# 17__schdoc.net
KiCad netlist of a schematic drawn in Altium Designer
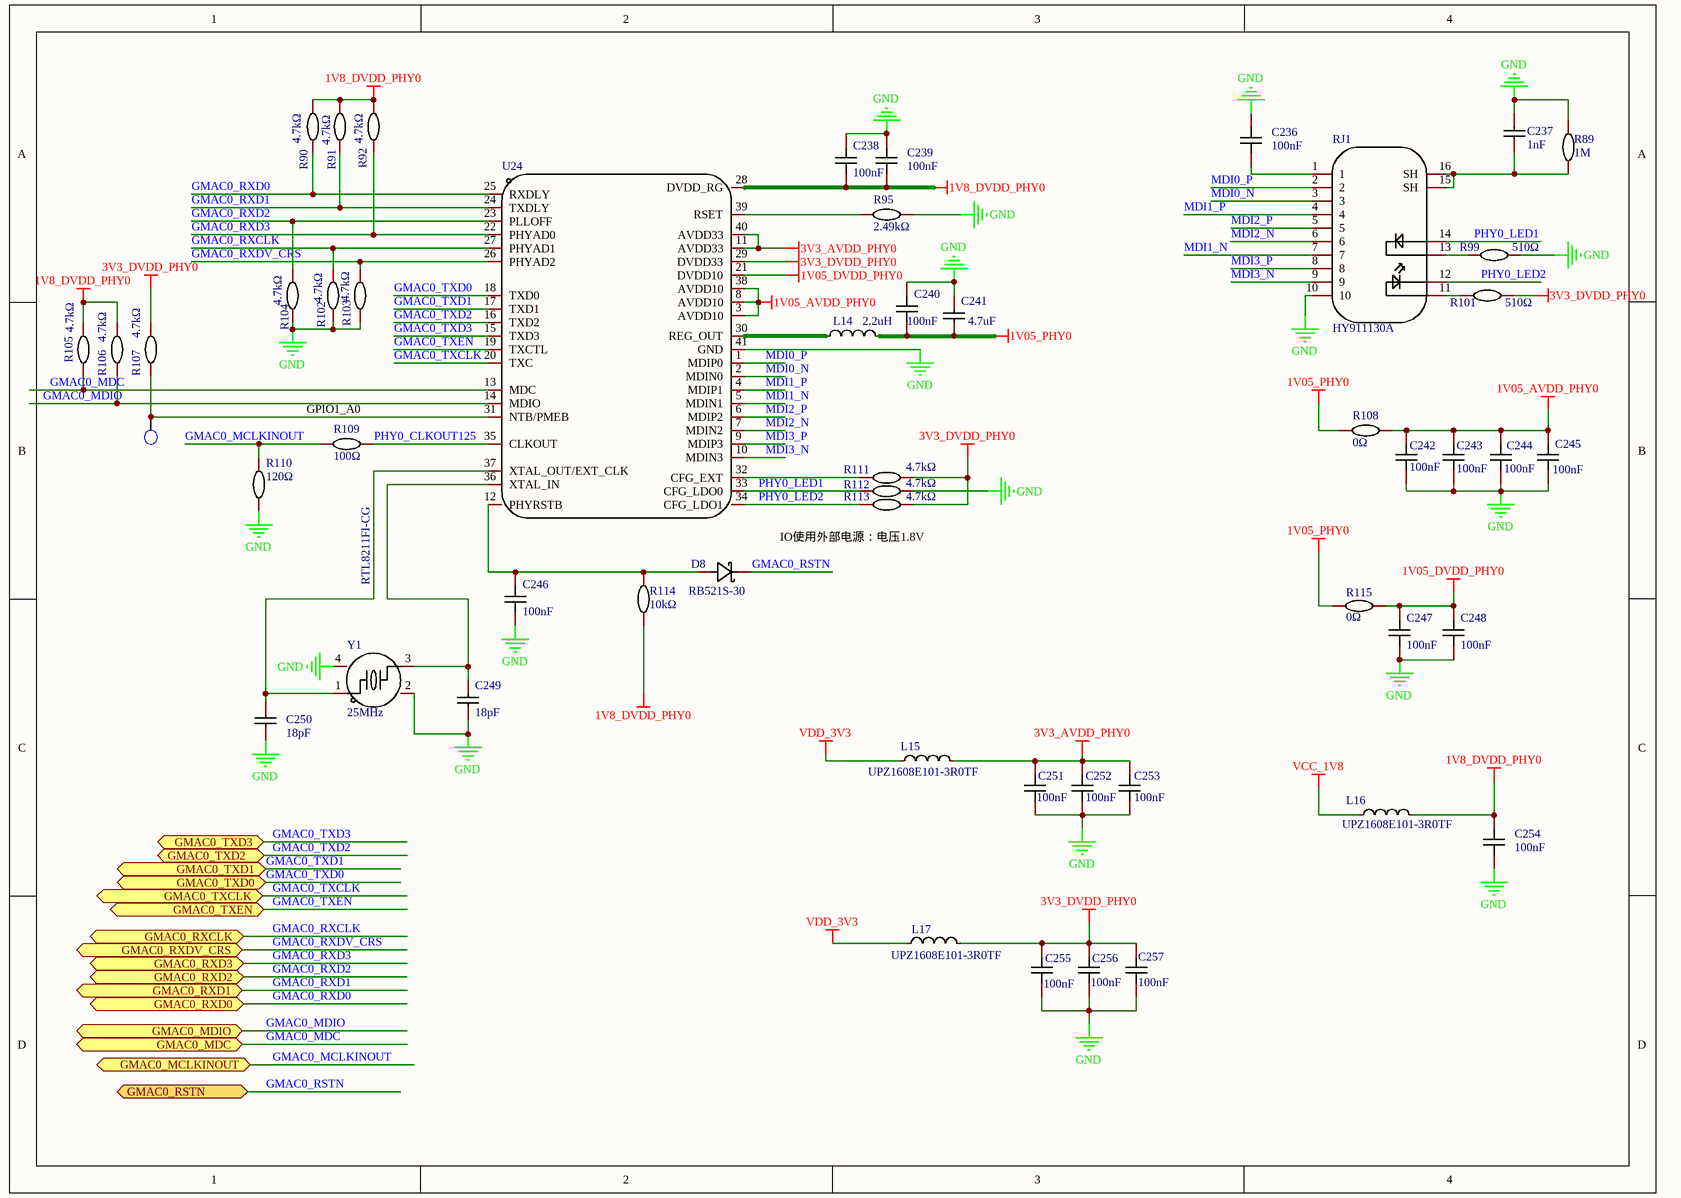
[diagram p0: 17_网口接口.schdoc.schdoc]

(export (version "E")
  (design (tool "Eeschema 10.0.6"))
  (components
    (comp (ref "C236")
      (value "100nF")
      (footprint "C0603")
      (fields
        (field (name "NAME") "100nF")
        (field (name "MANUFACTURER") "YAGEO(国巨)")
        (field (name "MANUFACTURER PART") "CC0603KRX7R9BB104")
        (field (name "TOLERANCE") "±10%")
      )
      (libsource (lib "altium-import") (part "root_1_CC0603KRX7R9BB104_"))
    )
    (comp (ref "C237")
      (value "1nF")
      (footprint "C0603")
      (fields
        (field (name "NAME") "1nF")
        (field (name "MANUFACTURER") "YAGEO(国巨)")
        (field (name "MANUFACTURER PART") "CC0603KRX7R9BB102")
        (field (name "TOLERANCE") "±10%")
      )
      (libsource (lib "altium-import") (part "root_3_CC0603KRX7R9BB102_"))
    )
    (comp (ref "C238")
      (value "100nF")
      (footprint "C0603")
      (fields
        (field (name "NAME") "100nF")
        (field (name "MANUFACTURER") "YAGEO(国巨)")
        (field (name "MANUFACTURER PART") "CC0603KRX7R9BB104")
        (field (name "TOLERANCE") "±10%")
      )
      (libsource (lib "altium-import") (part "root_1_CC0603KRX7R9BB104_"))
    )
    (comp (ref "C239")
      (value "100nF")
      (footprint "C0603")
      (fields
        (field (name "NAME") "100nF")
        (field (name "MANUFACTURER") "YAGEO(国巨)")
        (field (name "MANUFACTURER PART") "CC0603KRX7R9BB104")
        (field (name "TOLERANCE") "±10%")
      )
      (libsource (lib "altium-import") (part "root_1_CC0603KRX7R9BB104_"))
    )
    (comp (ref "C240")
      (value "100nF")
      (footprint "C0603")
      (fields
        (field (name "NAME") "100nF")
        (field (name "MANUFACTURER") "YAGEO(国巨)")
        (field (name "MANUFACTURER PART") "CC0603KRX7R9BB104")
        (field (name "TOLERANCE") "±10%")
      )
      (libsource (lib "altium-import") (part "root_1_CC0603KRX7R9BB104_"))
    )
    (comp (ref "C241")
      (value "4.7uF")
      (footprint "C0603")
      (fields
        (field (name "NAME") "4.7uF")
        (field (name "MANUFACTURER PART") "CL10A475KO8NNNC")
        (field (name "MANUFACTURER") "SAMSUNG(三星)")
        (field (name "TOLERANCE") "±10%")
      )
      (libsource (lib "altium-import") (part "root_1_CL10A475KO8NNNC_"))
    )
    (comp (ref "C242")
      (value "100nF")
      (footprint "C0603")
      (fields
        (field (name "NAME") "100nF")
        (field (name "MANUFACTURER") "YAGEO(国巨)")
        (field (name "MANUFACTURER PART") "CC0603KRX7R9BB104")
        (field (name "TOLERANCE") "±10%")
      )
      (libsource (lib "altium-import") (part "root_1_CC0603KRX7R9BB104_"))
    )
    (comp (ref "C243")
      (value "100nF")
      (footprint "C0603")
      (fields
        (field (name "NAME") "100nF")
        (field (name "MANUFACTURER") "YAGEO(国巨)")
        (field (name "MANUFACTURER PART") "CC0603KRX7R9BB104")
        (field (name "TOLERANCE") "±10%")
      )
      (libsource (lib "altium-import") (part "root_1_CC0603KRX7R9BB104_"))
    )
    (comp (ref "C244")
      (value "100nF")
      (footprint "C0603")
      (fields
        (field (name "NAME") "100nF")
        (field (name "MANUFACTURER") "YAGEO(国巨)")
        (field (name "MANUFACTURER PART") "CC0603KRX7R9BB104")
        (field (name "TOLERANCE") "±10%")
      )
      (libsource (lib "altium-import") (part "root_1_CC0603KRX7R9BB104_"))
    )
    (comp (ref "C245")
      (value "100nF")
      (footprint "C0603")
      (fields
        (field (name "NAME") "100nF")
        (field (name "MANUFACTURER") "YAGEO(国巨)")
        (field (name "MANUFACTURER PART") "CC0603KRX7R9BB104")
        (field (name "TOLERANCE") "±10%")
      )
      (libsource (lib "altium-import") (part "root_1_CC0603KRX7R9BB104_"))
    )
    (comp (ref "C246")
      (value "100nF")
      (footprint "C0603")
      (fields
        (field (name "NAME") "100nF")
        (field (name "MANUFACTURER") "YAGEO(国巨)")
        (field (name "MANUFACTURER PART") "CC0603KRX7R9BB104")
        (field (name "TOLERANCE") "±10%")
      )
      (libsource (lib "altium-import") (part "root_1_CC0603KRX7R9BB104_"))
    )
    (comp (ref "C247")
      (value "100nF")
      (footprint "C0603")
      (fields
        (field (name "NAME") "100nF")
        (field (name "MANUFACTURER") "YAGEO(国巨)")
        (field (name "MANUFACTURER PART") "CC0603KRX7R9BB104")
        (field (name "TOLERANCE") "±10%")
      )
      (libsource (lib "altium-import") (part "root_1_CC0603KRX7R9BB104_"))
    )
    (comp (ref "C248")
      (value "100nF")
      (footprint "C0603")
      (fields
        (field (name "NAME") "100nF")
        (field (name "MANUFACTURER") "YAGEO(国巨)")
        (field (name "MANUFACTURER PART") "CC0603KRX7R9BB104")
        (field (name "TOLERANCE") "±10%")
      )
      (libsource (lib "altium-import") (part "root_1_CC0603KRX7R9BB104_"))
    )
    (comp (ref "C249")
      (value "18pF")
      (footprint "C0603")
      (fields
        (field (name "NAME") "18pF")
        (field (name "MANUFACTURER") "SAMSUNG(三星)")
        (field (name "MANUFACTURER PART") "CL10C180JB8NNNC")
        (field (name "TOLERANCE") "±5%")
      )
      (libsource (lib "altium-import") (part "root_3_CL10C180JB8NNNC_"))
    )
    (comp (ref "C250")
      (value "18pF")
      (footprint "C0603")
      (fields
        (field (name "NAME") "18pF")
        (field (name "MANUFACTURER") "SAMSUNG(三星)")
        (field (name "MANUFACTURER PART") "CL10C180JB8NNNC")
        (field (name "TOLERANCE") "±5%")
      )
      (libsource (lib "altium-import") (part "root_3_CL10C180JB8NNNC_"))
    )
    (comp (ref "C251")
      (value "100nF")
      (footprint "C0603")
      (fields
        (field (name "NAME") "100nF")
        (field (name "MANUFACTURER") "YAGEO(国巨)")
        (field (name "MANUFACTURER PART") "CC0603KRX7R9BB104")
        (field (name "TOLERANCE") "±10%")
      )
      (libsource (lib "altium-import") (part "root_1_CC0603KRX7R9BB104_"))
    )
    (comp (ref "C252")
      (value "100nF")
      (footprint "C0603")
      (fields
        (field (name "NAME") "100nF")
        (field (name "MANUFACTURER") "YAGEO(国巨)")
        (field (name "MANUFACTURER PART") "CC0603KRX7R9BB104")
        (field (name "TOLERANCE") "±10%")
      )
      (libsource (lib "altium-import") (part "root_1_CC0603KRX7R9BB104_"))
    )
    (comp (ref "C253")
      (value "100nF")
      (footprint "C0603")
      (fields
        (field (name "NAME") "100nF")
        (field (name "MANUFACTURER") "YAGEO(国巨)")
        (field (name "MANUFACTURER PART") "CC0603KRX7R9BB104")
        (field (name "TOLERANCE") "±10%")
      )
      (libsource (lib "altium-import") (part "root_1_CC0603KRX7R9BB104_"))
    )
    (comp (ref "C254")
      (value "100nF")
      (footprint "C0603")
      (fields
        (field (name "NAME") "100nF")
        (field (name "MANUFACTURER") "YAGEO(国巨)")
        (field (name "MANUFACTURER PART") "CC0603KRX7R9BB104")
        (field (name "TOLERANCE") "±10%")
      )
      (libsource (lib "altium-import") (part "root_1_CC0603KRX7R9BB104_"))
    )
    (comp (ref "C255")
      (value "100nF")
      (footprint "C0603")
      (fields
        (field (name "NAME") "100nF")
        (field (name "MANUFACTURER") "YAGEO(国巨)")
        (field (name "MANUFACTURER PART") "CC0603KRX7R9BB104")
        (field (name "TOLERANCE") "±10%")
      )
      (libsource (lib "altium-import") (part "root_1_CC0603KRX7R9BB104_"))
    )
    (comp (ref "C256")
      (value "100nF")
      (footprint "C0603")
      (fields
        (field (name "NAME") "100nF")
        (field (name "MANUFACTURER") "YAGEO(国巨)")
        (field (name "MANUFACTURER PART") "CC0603KRX7R9BB104")
        (field (name "TOLERANCE") "±10%")
      )
      (libsource (lib "altium-import") (part "root_1_CC0603KRX7R9BB104_"))
    )
    (comp (ref "C257")
      (value "100nF")
      (footprint "C0603")
      (fields
        (field (name "NAME") "100nF")
        (field (name "MANUFACTURER") "YAGEO(国巨)")
        (field (name "MANUFACTURER PART") "CC0603KRX7R9BB104")
        (field (name "TOLERANCE") "±10%")
      )
      (libsource (lib "altium-import") (part "root_1_CC0603KRX7R9BB104_"))
    )
    (comp (ref "D8")
      (value "RB521S-30")
      (footprint "SOD-523_L1.2-W0.8-LS1.6-RD")
      (fields (field (name "NAME") "RB521S-30") (field (name "MANUFACTURER") "TWGMC(台湾迪嘉)"))
      (libsource (lib "altium-import") (part "root_2_RB521S-30_C727120_"))
    )
    (comp (ref "L14")
      (value "2.2uH")
      (footprint "IND-SMD_L2.5-W2.0-VLS252012CX-150M")
      (fields
        (field (name "NAME") "2.2uH")
        (field (name "MANUFACTURER") "cjiang(长江微电)")
        (field (name "MANUFACTURER PART") "FXLB252012-2R2-M")
        (field (name "TOLERANCE") "±20%")
      )
      (libsource (lib "altium-import") (part "root_0_FXLB252012-2R2-M_"))
    )
    (comp (ref "L15")
      (value "UPZ1608E101-3R0TF")
      (footprint "L0603")
      (fields
        (field (name "NAME") "UPZ1608E101-3R0TF")
        (field (name "MANUFACTURER") "Sunlord(顺络)")
        (field (name "TOLERANCE") "±25%")
      )
      (libsource (lib "altium-import") (part "root_0_mirrored_UPZ1608E101-3R0TF_"))
    )
    (comp (ref "L16")
      (value "UPZ1608E101-3R0TF")
      (footprint "L0603")
      (fields
        (field (name "NAME") "UPZ1608E101-3R0TF")
        (field (name "MANUFACTURER") "Sunlord(顺络)")
        (field (name "TOLERANCE") "±25%")
      )
      (libsource (lib "altium-import") (part "root_0_mirrored_UPZ1608E101-3R0TF_"))
    )
    (comp (ref "L17")
      (value "UPZ1608E101-3R0TF")
      (footprint "L0603")
      (fields
        (field (name "NAME") "UPZ1608E101-3R0TF")
        (field (name "MANUFACTURER") "Sunlord(顺络)")
        (field (name "TOLERANCE") "±25%")
      )
      (libsource (lib "altium-import") (part "root_0_mirrored_UPZ1608E101-3R0TF_"))
    )
    (comp (ref "R89")
      (value "1M")
      (footprint "R0805")
      (fields (field (name "NAME") "1M"))
      (libsource (lib "altium-import") (part "root_3_Res_0805_"))
    )
    (comp (ref "R90")
      (value "4.7kΩ")
      (footprint "R0603")
      (fields
        (field (name "NAME") "4.7kΩ")
        (field (name "MANUFACTURER") "UNI-ROYAL(厚声)")
        (field (name "MANUFACTURER PART") "0603WAF4701T5E")
        (field (name "TOLERANCE") "±1%")
      )
      (libsource (lib "altium-import") (part "root_1_0603WAF4701T5E_"))
    )
    (comp (ref "R91")
      (value "4.7kΩ")
      (footprint "R0603")
      (fields
        (field (name "NAME") "4.7kΩ")
        (field (name "MANUFACTURER") "UNI-ROYAL(厚声)")
        (field (name "MANUFACTURER PART") "0603WAF4701T5E")
        (field (name "TOLERANCE") "±1%")
      )
      (libsource (lib "altium-import") (part "root_1_0603WAF4701T5E_"))
    )
    (comp (ref "R92")
      (value "4.7kΩ")
      (footprint "R0603")
      (fields
        (field (name "NAME") "4.7kΩ")
        (field (name "MANUFACTURER") "UNI-ROYAL(厚声)")
        (field (name "MANUFACTURER PART") "0603WAF4701T5E")
        (field (name "TOLERANCE") "±1%")
      )
      (libsource (lib "altium-import") (part "root_1_0603WAF4701T5E_"))
    )
    (comp (ref "R95")
      (value "2.49kΩ")
      (footprint "R0603")
      (fields
        (field (name "NAME") "2.49kΩ")
        (field (name "MANUFACTURER") "UNI-ROYAL(厚声)")
        (field (name "MANUFACTURER PART") "0603WAF2491T5E")
        (field (name "TOLERANCE") "±1%")
      )
      (libsource (lib "altium-import") (part "root_0_0603WAF2491T5E_"))
    )
    (comp (ref "R99")
      (value "510Ω")
      (footprint "R0603")
      (fields
        (field (name "NAME") "510Ω")
        (field (name "MANUFACTURER") "UNI-ROYAL(厚声)")
        (field (name "MANUFACTURER PART") "0603WAF5100T5E")
        (field (name "TOLERANCE") "±1%")
      )
      (libsource (lib "altium-import") (part "root_0_0603WAF5100T5E_"))
    )
    (comp (ref "R101")
      (value "510Ω")
      (footprint "R0603")
      (fields
        (field (name "NAME") "510Ω")
        (field (name "MANUFACTURER") "UNI-ROYAL(厚声)")
        (field (name "MANUFACTURER PART") "0603WAF5100T5E")
        (field (name "TOLERANCE") "±1%")
      )
      (libsource (lib "altium-import") (part "root_0_0603WAF5100T5E_"))
    )
    (comp (ref "R102")
      (value "4.7kΩ")
      (footprint "R0603")
      (fields
        (field (name "NAME") "4.7kΩ")
        (field (name "MANUFACTURER") "UNI-ROYAL(厚声)")
        (field (name "MANUFACTURER PART") "0603WAF4701T5E")
        (field (name "TOLERANCE") "±1%")
      )
      (libsource (lib "altium-import") (part "root_1_0603WAF4701T5E_"))
    )
    (comp (ref "R103")
      (value "4.7kΩ")
      (footprint "R0603")
      (fields
        (field (name "NAME") "4.7kΩ")
        (field (name "MANUFACTURER") "UNI-ROYAL(厚声)")
        (field (name "MANUFACTURER PART") "0603WAF4701T5E")
        (field (name "TOLERANCE") "±1%")
      )
      (libsource (lib "altium-import") (part "root_1_0603WAF4701T5E_"))
    )
    (comp (ref "R104")
      (value "4.7kΩ")
      (footprint "R0603")
      (fields
        (field (name "NAME") "4.7kΩ")
        (field (name "MANUFACTURER") "UNI-ROYAL(厚声)")
        (field (name "MANUFACTURER PART") "0603WAF4701T5E")
        (field (name "TOLERANCE") "±1%")
      )
      (libsource (lib "altium-import") (part "root_1_0603WAF4701T5E_"))
    )
    (comp (ref "R105")
      (value "4.7kΩ")
      (footprint "R0603")
      (fields
        (field (name "NAME") "4.7kΩ")
        (field (name "MANUFACTURER") "UNI-ROYAL(厚声)")
        (field (name "MANUFACTURER PART") "0603WAF4701T5E")
        (field (name "TOLERANCE") "±1%")
      )
      (libsource (lib "altium-import") (part "root_1_0603WAF4701T5E_"))
    )
    (comp (ref "R106")
      (value "4.7kΩ")
      (footprint "R0603")
      (fields
        (field (name "NAME") "4.7kΩ")
        (field (name "MANUFACTURER") "UNI-ROYAL(厚声)")
        (field (name "MANUFACTURER PART") "0603WAF4701T5E")
        (field (name "TOLERANCE") "±1%")
      )
      (libsource (lib "altium-import") (part "root_1_0603WAF4701T5E_"))
    )
    (comp (ref "R107")
      (value "4.7kΩ")
      (footprint "R0603")
      (fields
        (field (name "NAME") "4.7kΩ")
        (field (name "MANUFACTURER") "UNI-ROYAL(厚声)")
        (field (name "MANUFACTURER PART") "0603WAF4701T5E")
        (field (name "TOLERANCE") "±1%")
      )
      (libsource (lib "altium-import") (part "root_1_0603WAF4701T5E_"))
    )
    (comp (ref "R108")
      (value "0Ω")
      (footprint "R0603")
      (fields
        (field (name "NAME") "0Ω")
        (field (name "MANUFACTURER") "UNI-ROYAL(厚声)")
        (field (name "MANUFACTURER PART") "0603WAF0000T5E")
        (field (name "TOLERANCE") "±1%")
      )
      (libsource (lib "altium-import") (part "root_0_0603WAF0000T5E_"))
    )
    (comp (ref "R109")
      (value "100Ω")
      (footprint "R0603")
      (fields
        (field (name "NAME") "100Ω")
        (field (name "MANUFACTURER") "UNI-ROYAL(厚声)")
        (field (name "MANUFACTURER PART") "0603WAF1000T5E")
        (field (name "TOLERANCE") "±1%")
      )
      (libsource (lib "altium-import") (part "root_0_0603WAF1000T5E_"))
    )
    (comp (ref "R110")
      (value "120Ω")
      (footprint "R0603")
      (fields
        (field (name "NAME") "120Ω")
        (field (name "MANUFACTURER") "UNI-ROYAL(厚声)")
        (field (name "MANUFACTURER PART") "0603WAF1200T5E")
        (field (name "TOLERANCE") "±1%")
      )
      (libsource (lib "altium-import") (part "root_1_0603WAF1200T5E_"))
    )
    (comp (ref "R111")
      (value "4.7kΩ")
      (footprint "R0603")
      (fields
        (field (name "NAME") "4.7kΩ")
        (field (name "MANUFACTURER") "UNI-ROYAL(厚声)")
        (field (name "MANUFACTURER PART") "0603WAF4701T5E")
        (field (name "TOLERANCE") "±1%")
      )
      (libsource (lib "altium-import") (part "root_0_0603WAF4701T5E_"))
    )
    (comp (ref "R112")
      (value "4.7kΩ")
      (footprint "R0603")
      (fields
        (field (name "NAME") "4.7kΩ")
        (field (name "MANUFACTURER") "UNI-ROYAL(厚声)")
        (field (name "MANUFACTURER PART") "0603WAF4701T5E")
        (field (name "TOLERANCE") "±1%")
      )
      (libsource (lib "altium-import") (part "root_0_0603WAF4701T5E_"))
    )
    (comp (ref "R113")
      (value "4.7kΩ")
      (footprint "R0603")
      (fields
        (field (name "NAME") "4.7kΩ")
        (field (name "MANUFACTURER") "UNI-ROYAL(厚声)")
        (field (name "MANUFACTURER PART") "0603WAF4701T5E")
        (field (name "TOLERANCE") "±1%")
      )
      (libsource (lib "altium-import") (part "root_0_0603WAF4701T5E_"))
    )
    (comp (ref "R114")
      (value "10kΩ")
      (footprint "R0603")
      (fields
        (field (name "NAME") "10kΩ")
        (field (name "MANUFACTURER") "UNI-ROYAL(厚声)")
        (field (name "MANUFACTURER PART") "0603WAF1002T5E")
        (field (name "TOLERANCE") "±1%")
      )
      (libsource (lib "altium-import") (part "root_3_0603WAF1002T5E_"))
    )
    (comp (ref "R115")
      (value "0Ω")
      (footprint "R0603")
      (fields
        (field (name "NAME") "0Ω")
        (field (name "MANUFACTURER") "UNI-ROYAL(厚声)")
        (field (name "MANUFACTURER PART") "0603WAF0000T5E")
        (field (name "TOLERANCE") "±1%")
      )
      (libsource (lib "altium-import") (part "root_2_0603WAF0000T5E_"))
    )
    (comp (ref "RJ1")
      (value "HY911130A")
      (footprint "RJ45-TH_10P-P2.54-S2.54_L16.1-W21.4_HY911130A")
      (fields (field (name "NAME") "HY911130A") (field (name "MANUFACTURER") "HANRUN(汉仁)"))
      (libsource (lib "altium-import") (part "root_0_HY911130A_"))
    )
    (comp (ref "TP1") (value "TP") (footprint "TP_0R70") (libsource (lib "RK3568核心板") (part "TP")))
    (comp (ref "U24")
      (value "RTL8211FI-CG")
      (footprint "QFN-40_L5.0-W5.0-P0.40-BL-EP3.7")
      (fields (field (name "NAME") "RTL8211FI-CG") (field (name "MANUFACTURER") "REALTEK(瑞昱)"))
      (libsource (lib "altium-import") (part "root_0_RTL8211FI-CG_"))
    )
    (comp (ref "Y1")
      (value "25MHz")
      (footprint "CRYSTAL-SMD_4P-L3.2-W2.5-BL")
      (fields
        (field (name "NAME") "25MHz")
        (field (name "MANUFACTURER") "YXC(扬兴晶振)")
        (field (name "MANUFACTURER PART") "XL2EL89CSI-111YLC-25M")
      )
      (libsource (lib "altium-import") (part "root_0_XL2EL89CSI-111YLC-25M_"))
    )
  )
  (nets
    (net (code "1") (name "/GMAC0_MCLKINOUT") (class "Default")
      (node (ref "R109") (pin "1") (pinfunction "1_1") (pintype "passive"))
      (node (ref "R110") (pin "2") (pinfunction "2_2") (pintype "passive"))
    )
    (net (code "2") (name "/GMAC0_MDC") (class "Default")
      (node (ref "R105") (pin "1") (pinfunction "1_1") (pintype "passive"))
      (node (ref "U24") (pin "13") (pinfunction "MDC_13") (pintype "passive"))
    )
    (net (code "3") (name "/GMAC0_MDIO") (class "Default")
      (node (ref "R106") (pin "1") (pinfunction "1_1") (pintype "passive"))
      (node (ref "U24") (pin "14") (pinfunction "MDIO_14") (pintype "passive"))
    )
    (net (code "4") (name "/GMAC0_RSTN") (class "Default")
      (node (ref "D8") (pin "1") (pinfunction "K_1") (pintype "passive"))
    )
    (net (code "5") (name "/GMAC0_RXCLK") (class "Default")
      (node (ref "R102") (pin "2") (pinfunction "2_2") (pintype "passive"))
      (node (ref "U24") (pin "27") (pinfunction "PHYAD1_27") (pintype "passive"))
    )
    (net (code "6") (name "/GMAC0_RXD0") (class "Default")
      (node (ref "R90") (pin "1") (pinfunction "1_1") (pintype "passive"))
      (node (ref "U24") (pin "25") (pinfunction "RXDLY_25") (pintype "passive"))
    )
    (net (code "7") (name "/GMAC0_RXD1") (class "Default")
      (node (ref "R91") (pin "1") (pinfunction "1_1") (pintype "passive"))
      (node (ref "U24") (pin "24") (pinfunction "TXDLY_24") (pintype "passive"))
    )
    (net (code "8") (name "/GMAC0_RXD2") (class "Default")
      (node (ref "R104") (pin "2") (pinfunction "2_2") (pintype "passive"))
      (node (ref "U24") (pin "23") (pinfunction "PLLOFF_23") (pintype "passive"))
    )
    (net (code "9") (name "/GMAC0_RXD3") (class "Default")
      (node (ref "R92") (pin "1") (pinfunction "1_1") (pintype "passive"))
      (node (ref "U24") (pin "22") (pinfunction "PHYAD0_22") (pintype "passive"))
    )
    (net (code "10") (name "/GMAC0_RXDV_CRS") (class "Default")
      (node (ref "R103") (pin "2") (pinfunction "2_2") (pintype "passive"))
      (node (ref "U24") (pin "26") (pinfunction "PHYAD2_26") (pintype "passive"))
    )
    (net (code "11") (name "/GMAC0_TXCLK") (class "Default")
      (node (ref "U24") (pin "20") (pinfunction "TXC_20") (pintype "passive"))
    )
    (net (code "12") (name "/GMAC0_TXD0") (class "Default")
      (node (ref "U24") (pin "18") (pinfunction "TXD0_18") (pintype "passive"))
    )
    (net (code "13") (name "/GMAC0_TXD1") (class "Default")
      (node (ref "U24") (pin "17") (pinfunction "TXD1_17") (pintype "passive"))
    )
    (net (code "14") (name "/GMAC0_TXD2") (class "Default")
      (node (ref "U24") (pin "16") (pinfunction "TXD2_16") (pintype "passive"))
    )
    (net (code "15") (name "/GMAC0_TXD3") (class "Default")
      (node (ref "U24") (pin "15") (pinfunction "TXD3_15") (pintype "passive"))
    )
    (net (code "16") (name "/GMAC0_TXEN") (class "Default")
      (node (ref "U24") (pin "19") (pinfunction "TXCTL_19") (pintype "passive"))
    )
    (net (code "17") (name "/MDI0_N") (class "Default")
      (node (ref "RJ1") (pin "3") (pinfunction "3_3") (pintype "passive"))
      (node (ref "U24") (pin "2") (pinfunction "MDIN0_2") (pintype "passive"))
    )
    (net (code "18") (name "/MDI0_P") (class "Default")
      (node (ref "RJ1") (pin "2") (pinfunction "2_2") (pintype "passive"))
      (node (ref "U24") (pin "1") (pinfunction "MDIP0_1") (pintype "passive"))
    )
    (net (code "19") (name "/MDI1_N") (class "Default")
      (node (ref "RJ1") (pin "7") (pinfunction "7_7") (pintype "passive"))
      (node (ref "U24") (pin "5") (pinfunction "MDIN1_5") (pintype "passive"))
    )
    (net (code "20") (name "/MDI1_P") (class "Default")
      (node (ref "RJ1") (pin "4") (pinfunction "4_4") (pintype "passive"))
      (node (ref "U24") (pin "4") (pinfunction "MDIP1_4") (pintype "passive"))
    )
    (net (code "21") (name "/MDI2_N") (class "Default")
      (node (ref "RJ1") (pin "6") (pinfunction "6_6") (pintype "passive"))
      (node (ref "U24") (pin "7") (pinfunction "MDIN2_7") (pintype "passive"))
    )
    (net (code "22") (name "/MDI2_P") (class "Default")
      (node (ref "RJ1") (pin "5") (pinfunction "5_5") (pintype "passive"))
      (node (ref "U24") (pin "6") (pinfunction "MDIP2_6") (pintype "passive"))
    )
    (net (code "23") (name "/MDI3_N") (class "Default")
      (node (ref "RJ1") (pin "9") (pinfunction "9_9") (pintype "passive"))
      (node (ref "U24") (pin "10") (pinfunction "MDIN3_10") (pintype "passive"))
    )
    (net (code "24") (name "/MDI3_P") (class "Default")
      (node (ref "RJ1") (pin "8") (pinfunction "8_8") (pintype "passive"))
      (node (ref "U24") (pin "9") (pinfunction "MDIP3_9") (pintype "passive"))
    )
    (net (code "25") (name "/PHY0_CLKOUT125") (class "Default")
      (node (ref "R109") (pin "2") (pinfunction "2_2") (pintype "passive"))
      (node (ref "U24") (pin "35") (pinfunction "CLKOUT_35") (pintype "passive"))
    )
    (net (code "26") (name "/PHY0_LED1") (class "Default")
      (node (ref "R112") (pin "1") (pinfunction "1_1") (pintype "passive"))
      (node (ref "RJ1") (pin "14") (pinfunction "14_14") (pintype "passive"))
      (node (ref "U24") (pin "33") (pinfunction "CFG_LDO0_33") (pintype "passive"))
    )
    (net (code "27") (name "/PHY0_LED2") (class "Default")
      (node (ref "R113") (pin "1") (pinfunction "1_1") (pintype "passive"))
      (node (ref "RJ1") (pin "12") (pinfunction "12_12") (pintype "passive"))
      (node (ref "U24") (pin "34") (pinfunction "CFG_LDO1_34") (pintype "passive"))
    )
    (net (code "28") (name "1V05_AVDD_PHY0") (class "Default")
      (node (ref "C242") (pin "2") (pinfunction "2_2") (pintype "passive"))
      (node (ref "C243") (pin "2") (pinfunction "2_2") (pintype "passive"))
      (node (ref "C244") (pin "2") (pinfunction "2_2") (pintype "passive"))
      (node (ref "C245") (pin "2") (pinfunction "2_2") (pintype "passive"))
      (node (ref "R108") (pin "2") (pinfunction "2_2") (pintype "passive"))
      (node (ref "U24") (pin "3") (pinfunction "AVDD10_3") (pintype "passive"))
      (node (ref "U24") (pin "38") (pinfunction "AVDD10_38") (pintype "passive"))
      (node (ref "U24") (pin "8") (pinfunction "AVDD10_8") (pintype "passive"))
    )
    (net (code "29") (name "1V05_DVDD_PHY0") (class "Default")
      (node (ref "C247") (pin "2") (pinfunction "2_2") (pintype "passive"))
      (node (ref "C248") (pin "2") (pinfunction "2_2") (pintype "passive"))
      (node (ref "R115") (pin "1") (pinfunction "1_1") (pintype "passive"))
      (node (ref "U24") (pin "21") (pinfunction "DVDD10_21") (pintype "passive"))
    )
    (net (code "30") (name "1V05_PHY0") (class "Default")
      (node (ref "C240") (pin "1") (pinfunction "1_1") (pintype "passive"))
      (node (ref "C241") (pin "1") (pinfunction "1_1") (pintype "passive"))
      (node (ref "L14") (pin "2") (pinfunction "2_2") (pintype "passive"))
      (node (ref "R108") (pin "1") (pinfunction "1_1") (pintype "passive"))
      (node (ref "R115") (pin "2") (pinfunction "2_2") (pintype "passive"))
    )
    (net (code "31") (name "1V8_DVDD_PHY0") (class "Default")
      (node (ref "C238") (pin "1") (pinfunction "1_1") (pintype "passive"))
      (node (ref "C239") (pin "1") (pinfunction "1_1") (pintype "passive"))
      (node (ref "C254") (pin "2") (pinfunction "2_2") (pintype "passive"))
      (node (ref "L16") (pin "1") (pinfunction "1_1") (pintype "passive"))
      (node (ref "R105") (pin "2") (pinfunction "2_2") (pintype "passive"))
      (node (ref "R106") (pin "2") (pinfunction "2_2") (pintype "passive"))
      (node (ref "R114") (pin "2") (pinfunction "2_2") (pintype "passive"))
      (node (ref "R90") (pin "2") (pinfunction "2_2") (pintype "passive"))
      (node (ref "R91") (pin "2") (pinfunction "2_2") (pintype "passive"))
      (node (ref "R92") (pin "2") (pinfunction "2_2") (pintype "passive"))
      (node (ref "U24") (pin "28") (pinfunction "DVDD_RG_28") (pintype "passive"))
    )
    (net (code "32") (name "3V3_AVDD_PHY0") (class "Default")
      (node (ref "C251") (pin "2") (pinfunction "2_2") (pintype "passive"))
      (node (ref "C252") (pin "2") (pinfunction "2_2") (pintype "passive"))
      (node (ref "C253") (pin "2") (pinfunction "2_2") (pintype "passive"))
      (node (ref "L15") (pin "1") (pinfunction "1_1") (pintype "passive"))
      (node (ref "U24") (pin "11") (pinfunction "AVDD33_11") (pintype "passive"))
      (node (ref "U24") (pin "40") (pinfunction "AVDD33_40") (pintype "passive"))
    )
    (net (code "33") (name "3V3_DVDD_PHY0") (class "Default")
      (node (ref "C255") (pin "2") (pinfunction "2_2") (pintype "passive"))
      (node (ref "C256") (pin "2") (pinfunction "2_2") (pintype "passive"))
      (node (ref "C257") (pin "2") (pinfunction "2_2") (pintype "passive"))
      (node (ref "L17") (pin "1") (pinfunction "1_1") (pintype "passive"))
      (node (ref "R101") (pin "2") (pinfunction "2_2") (pintype "passive"))
      (node (ref "R107") (pin "2") (pinfunction "2_2") (pintype "passive"))
      (node (ref "R111") (pin "2") (pinfunction "2_2") (pintype "passive"))
      (node (ref "R113") (pin "2") (pinfunction "2_2") (pintype "passive"))
      (node (ref "U24") (pin "29") (pinfunction "DVDD33_29") (pintype "passive"))
    )
    (net (code "34") (name "GND") (class "Default")
      (node (ref "C236") (pin "2") (pinfunction "2_2") (pintype "passive"))
      (node (ref "C237") (pin "1") (pinfunction "1_1") (pintype "passive"))
      (node (ref "C238") (pin "2") (pinfunction "2_2") (pintype "passive"))
      (node (ref "C239") (pin "2") (pinfunction "2_2") (pintype "passive"))
      (node (ref "C240") (pin "2") (pinfunction "2_2") (pintype "passive"))
      (node (ref "C241") (pin "2") (pinfunction "2_2") (pintype "passive"))
      (node (ref "C242") (pin "1") (pinfunction "1_1") (pintype "passive"))
      (node (ref "C243") (pin "1") (pinfunction "1_1") (pintype "passive"))
      (node (ref "C244") (pin "1") (pinfunction "1_1") (pintype "passive"))
      (node (ref "C245") (pin "1") (pinfunction "1_1") (pintype "passive"))
      (node (ref "C246") (pin "1") (pinfunction "1_1") (pintype "passive"))
      (node (ref "C247") (pin "1") (pinfunction "1_1") (pintype "passive"))
      (node (ref "C248") (pin "1") (pinfunction "1_1") (pintype "passive"))
      (node (ref "C249") (pin "2") (pinfunction "2_2") (pintype "passive"))
      (node (ref "C250") (pin "2") (pinfunction "2_2") (pintype "passive"))
      (node (ref "C251") (pin "1") (pinfunction "1_1") (pintype "passive"))
      (node (ref "C252") (pin "1") (pinfunction "1_1") (pintype "passive"))
      (node (ref "C253") (pin "1") (pinfunction "1_1") (pintype "passive"))
      (node (ref "C254") (pin "1") (pinfunction "1_1") (pintype "passive"))
      (node (ref "C255") (pin "1") (pinfunction "1_1") (pintype "passive"))
      (node (ref "C256") (pin "1") (pinfunction "1_1") (pintype "passive"))
      (node (ref "C257") (pin "1") (pinfunction "1_1") (pintype "passive"))
      (node (ref "R102") (pin "1") (pinfunction "1_1") (pintype "passive"))
      (node (ref "R103") (pin "1") (pinfunction "1_1") (pintype "passive"))
      (node (ref "R104") (pin "1") (pinfunction "1_1") (pintype "passive"))
      (node (ref "R110") (pin "1") (pinfunction "1_1") (pintype "passive"))
      (node (ref "R112") (pin "2") (pinfunction "2_2") (pintype "passive"))
      (node (ref "R89") (pin "1") (pinfunction "1_1") (pintype "passive"))
      (node (ref "R95") (pin "2") (pinfunction "2_2") (pintype "passive"))
      (node (ref "R99") (pin "2") (pinfunction "2_2") (pintype "passive"))
      (node (ref "RJ1") (pin "10") (pinfunction "10_10") (pintype "passive"))
      (node (ref "U24") (pin "41") (pinfunction "GND_41") (pintype "passive"))
      (node (ref "Y1") (pin "2") (pinfunction "GND_2") (pintype "passive"))
      (node (ref "Y1") (pin "4") (pinfunction "GND_4") (pintype "passive"))
    )
    (net (code "35") (name "Net-(C236-Pad1)") (class "Default")
      (node (ref "C236") (pin "1") (pinfunction "1_1") (pintype "passive"))
      (node (ref "RJ1") (pin "1") (pinfunction "1_1") (pintype "passive"))
    )
    (net (code "36") (name "Net-(C237-Pad2)") (class "Default")
      (node (ref "C237") (pin "2") (pinfunction "2_2") (pintype "passive"))
      (node (ref "R89") (pin "2") (pinfunction "2_2") (pintype "passive"))
      (node (ref "RJ1") (pin "15") (pinfunction "SH_15") (pintype "passive"))
      (node (ref "RJ1") (pin "16") (pinfunction "SH_16") (pintype "passive"))
    )
    (net (code "37") (name "Net-(D8-A)") (class "Default")
      (node (ref "C246") (pin "2") (pinfunction "2_2") (pintype "passive"))
      (node (ref "D8") (pin "2") (pinfunction "A_2") (pintype "passive"))
      (node (ref "R114") (pin "1") (pinfunction "1_1") (pintype "passive"))
      (node (ref "U24") (pin "12") (pinfunction "PHYRSTB_12") (pintype "passive"))
    )
    (net (code "38") (name "Net-(R99-Pad1)") (class "Default")
      (node (ref "R99") (pin "1") (pinfunction "1_1") (pintype "passive"))
      (node (ref "RJ1") (pin "13") (pinfunction "13_13") (pintype "passive"))
    )
    (net (code "39") (name "Net-(R101-Pad1)") (class "Default")
      (node (ref "R101") (pin "1") (pinfunction "1_1") (pintype "passive"))
      (node (ref "RJ1") (pin "11") (pinfunction "11_11") (pintype "passive"))
    )
    (net (code "40") (name "Net-(U24-CFG_EXT)") (class "Default")
      (node (ref "R111") (pin "1") (pinfunction "1_1") (pintype "passive"))
      (node (ref "U24") (pin "32") (pinfunction "CFG_EXT_32") (pintype "passive"))
    )
    (net (code "41") (name "Net-(U24-NTB{slash}PMEB)") (class "Default")
      (node (ref "R107") (pin "1") (pinfunction "1_1") (pintype "passive"))
      (node (ref "TP1") (pin "1") (pinfunction "1_1") (pintype "passive"))
      (node (ref "U24") (pin "31") (pinfunction "NTB/PMEB_31") (pintype "passive"))
    )
    (net (code "42") (name "Net-(U24-REG_OUT)") (class "Default")
      (node (ref "L14") (pin "1") (pinfunction "1_1") (pintype "passive"))
      (node (ref "U24") (pin "30") (pinfunction "REG_OUT_30") (pintype "passive"))
    )
    (net (code "43") (name "Net-(U24-RSET)") (class "Default")
      (node (ref "R95") (pin "1") (pinfunction "1_1") (pintype "passive"))
      (node (ref "U24") (pin "39") (pinfunction "RSET_39") (pintype "passive"))
    )
    (net (code "44") (name "Net-(U24-XTAL_IN)") (class "Default")
      (node (ref "C249") (pin "1") (pinfunction "1_1") (pintype "passive"))
      (node (ref "U24") (pin "36") (pinfunction "XTAL_IN_36") (pintype "passive"))
      (node (ref "Y1") (pin "3") (pinfunction "3_3") (pintype "passive"))
    )
    (net (code "45") (name "Net-(U24-XTAL_OUT{slash}EXT_CLK)") (class "Default")
      (node (ref "C250") (pin "1") (pinfunction "1_1") (pintype "passive"))
      (node (ref "U24") (pin "37") (pinfunction "XTAL_OUT/EXT_CLK_37") (pintype "passive"))
      (node (ref "Y1") (pin "1") (pinfunction "1_1") (pintype "passive"))
    )
    (net (code "46") (name "VCC_1V8") (class "Default")
      (node (ref "L16") (pin "2") (pinfunction "2_2") (pintype "passive"))
    )
    (net (code "47") (name "VDD_3V3") (class "Default")
      (node (ref "L15") (pin "2") (pinfunction "2_2") (pintype "passive"))
      (node (ref "L17") (pin "2") (pinfunction "2_2") (pintype "passive"))
    )
  )
)
